# Tom_Casey.net
KiCad netlist of a schematic drawn in EAGLE
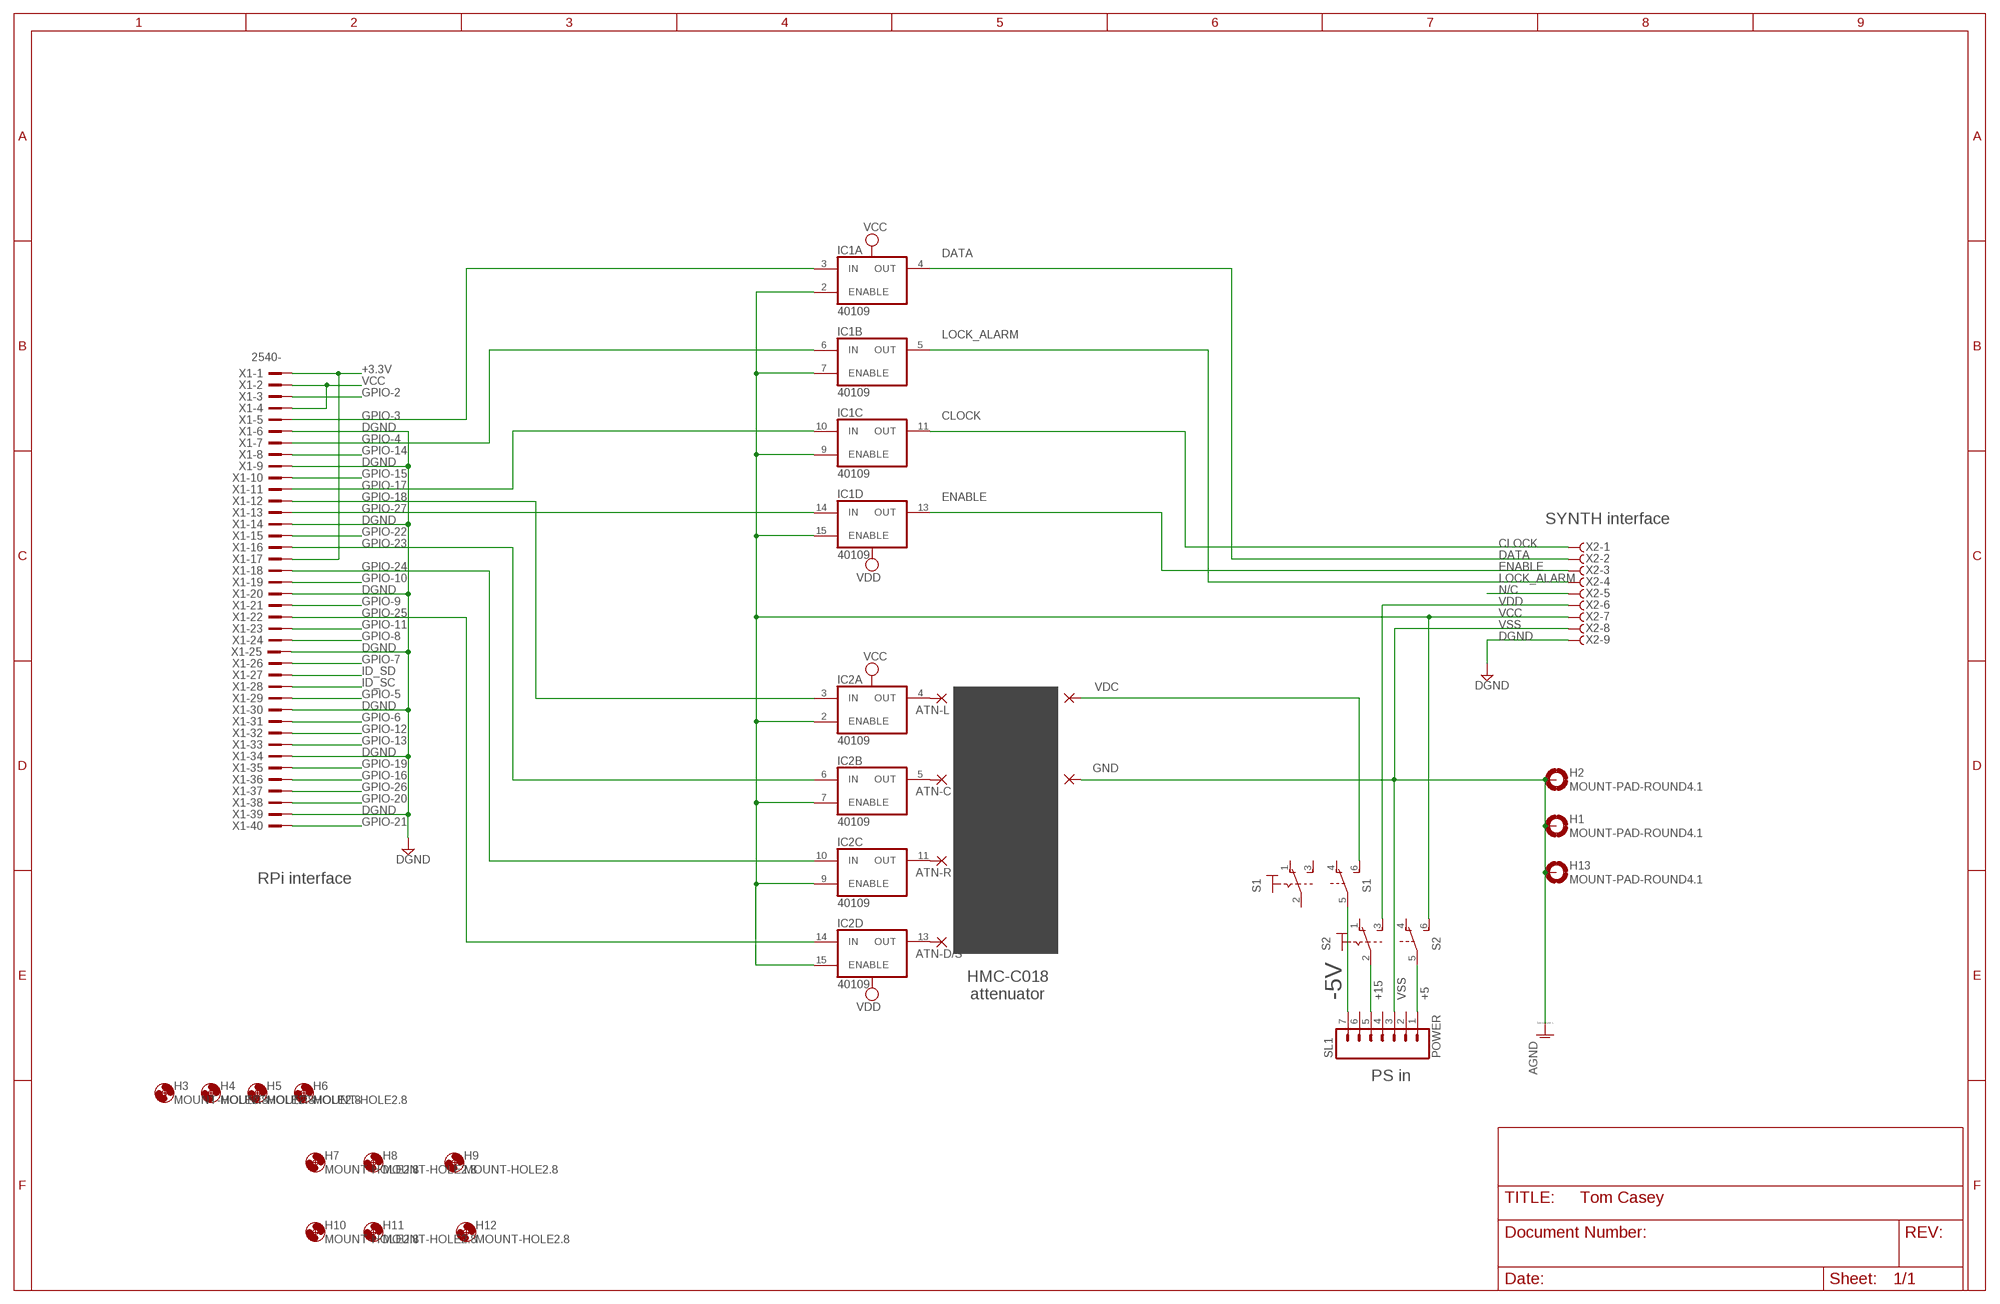
[diagram p0: schematic, sheet 1]

(export (version "E")
  (design (tool "Eeschema 10.0.6"))
  (components
    (comp (ref "ATN-C")
      (value "PAD-0400")
      (footprint "eagle-import:0400")
      (libsource (lib "eagle-import") (part "PAD-0400"))
    )
    (comp (ref "ATN-D/S")
      (value "PAD-0400")
      (footprint "eagle-import:0400")
      (libsource (lib "eagle-import") (part "PAD-0400"))
    )
    (comp (ref "ATN-L")
      (value "PAD-0400")
      (footprint "eagle-import:0400")
      (libsource (lib "eagle-import") (part "PAD-0400"))
    )
    (comp (ref "ATN-R")
      (value "PAD-0400")
      (footprint "eagle-import:0400")
      (libsource (lib "eagle-import") (part "PAD-0400"))
    )
    (comp (ref "GND")
      (value "PAD-0400")
      (footprint "eagle-import:0400")
      (libsource (lib "eagle-import") (part "PAD-0400"))
    )
    (comp (ref "H1")
      (value "MOUNT-PAD-ROUND4.1")
      (footprint "eagle-import:4,1-PAD")
      (libsource (lib "eagle-import") (part "MOUNT-PAD-ROUND4.1"))
    )
    (comp (ref "H2")
      (value "MOUNT-PAD-ROUND4.1")
      (footprint "eagle-import:4,1-PAD")
      (libsource (lib "eagle-import") (part "MOUNT-PAD-ROUND4.1"))
    )
    (comp (ref "H3")
      (value "MOUNT-HOLE2.8")
      (footprint "eagle-import:2,8")
      (libsource (lib "eagle-import") (part "MOUNT-HOLE2.8"))
    )
    (comp (ref "H4")
      (value "MOUNT-HOLE2.8")
      (footprint "eagle-import:2,8")
      (libsource (lib "eagle-import") (part "MOUNT-HOLE2.8"))
    )
    (comp (ref "H5")
      (value "MOUNT-HOLE2.8")
      (footprint "eagle-import:2,8")
      (libsource (lib "eagle-import") (part "MOUNT-HOLE2.8"))
    )
    (comp (ref "H6")
      (value "MOUNT-HOLE2.8")
      (footprint "eagle-import:2,8")
      (libsource (lib "eagle-import") (part "MOUNT-HOLE2.8"))
    )
    (comp (ref "H7")
      (value "MOUNT-HOLE2.8")
      (footprint "eagle-import:2,8")
      (libsource (lib "eagle-import") (part "MOUNT-HOLE2.8"))
    )
    (comp (ref "H8")
      (value "MOUNT-HOLE2.8")
      (footprint "eagle-import:2,8")
      (libsource (lib "eagle-import") (part "MOUNT-HOLE2.8"))
    )
    (comp (ref "H9")
      (value "MOUNT-HOLE2.8")
      (footprint "eagle-import:2,8")
      (libsource (lib "eagle-import") (part "MOUNT-HOLE2.8"))
    )
    (comp (ref "H10")
      (value "MOUNT-HOLE2.8")
      (footprint "eagle-import:2,8")
      (libsource (lib "eagle-import") (part "MOUNT-HOLE2.8"))
    )
    (comp (ref "H11")
      (value "MOUNT-HOLE2.8")
      (footprint "eagle-import:2,8")
      (libsource (lib "eagle-import") (part "MOUNT-HOLE2.8"))
    )
    (comp (ref "H12")
      (value "MOUNT-HOLE2.8")
      (footprint "eagle-import:2,8")
      (libsource (lib "eagle-import") (part "MOUNT-HOLE2.8"))
    )
    (comp (ref "H13")
      (value "MOUNT-PAD-ROUND4.1")
      (footprint "eagle-import:4,1-PAD")
      (libsource (lib "eagle-import") (part "MOUNT-PAD-ROUND4.1"))
    )
    (comp (ref "IC1")
      (value "40109")
      (footprint "eagle-import:DIL16")
      (libsource (lib "eagle-import") (part "40109"))
    )
    (comp (ref "IC2")
      (value "40109")
      (footprint "eagle-import:DIL16")
      (libsource (lib "eagle-import") (part "40109"))
    )
    (comp (ref "S1")
      (value "M9040P2")
      (footprint "eagle-import:M9040P2")
      (libsource (lib "eagle-import") (part "M9040P2"))
    )
    (comp (ref "S2")
      (value "M9040P2")
      (footprint "eagle-import:M9040P2")
      (libsource (lib "eagle-import") (part "M9040P2"))
    )
    (comp (ref "SL1")
      (value "POWER")
      (footprint "eagle-import:07P")
      (libsource (lib "eagle-import") (part "M07"))
    )
    (comp (ref "VDC")
      (value "PAD-0400")
      (footprint "eagle-import:0400")
      (libsource (lib "eagle-import") (part "PAD-0400"))
    )
    (comp (ref "X1")
      (value "2540-")
      (footprint "eagle-import:PAK100_2500-40")
      (libsource (lib "eagle-import") (part "2540-"))
    )
    (comp (ref "X2")
      (value "F09HPS")
      (footprint "eagle-import:F09HP")
      (libsource (lib "eagle-import") (part "F09?SHP"))
    )
  )
  (nets
    (net (code "1") (name "/+3.3V") (class "Default")
      (node (ref "X1") (pin "1") (pinfunction "KL_1") (pintype "passive"))
      (node (ref "X1") (pin "17") (pinfunction "KL_17") (pintype "passive"))
    )
    (net (code "2") (name "/+5") (class "Default")
      (node (ref "S2") (pin "5") (pinfunction "P_5") (pintype "passive"))
      (node (ref "SL1") (pin "1") (pinfunction "1_1") (pintype "passive"))
    )
    (net (code "3") (name "/+15") (class "Default")
      (node (ref "S2") (pin "2") (pinfunction "P_2") (pintype "passive"))
      (node (ref "SL1") (pin "5") (pinfunction "5_5") (pintype "passive"))
    )
    (net (code "4") (name "/-5V") (class "Default")
      (node (ref "S1") (pin "5") (pinfunction "P_5") (pintype "passive"))
      (node (ref "SL1") (pin "7") (pinfunction "7_7") (pintype "passive"))
    )
    (net (code "5") (name "/CLOCK") (class "Default")
      (node (ref "IC1") (pin "11") (pinfunction "OUT_11") (pintype "tri_state"))
      (node (ref "X2") (pin "1") (pinfunction "F_1") (pintype "passive"))
    )
    (net (code "6") (name "/DATA") (class "Default")
      (node (ref "IC1") (pin "4") (pinfunction "OUT_4") (pintype "tri_state"))
      (node (ref "X2") (pin "2") (pinfunction "F_2") (pintype "passive"))
    )
    (net (code "7") (name "/ENABLE") (class "Default")
      (node (ref "IC1") (pin "13") (pinfunction "OUT_13") (pintype "tri_state"))
      (node (ref "X2") (pin "3") (pinfunction "F_3") (pintype "passive"))
    )
    (net (code "8") (name "/GPIO-2") (class "Default")
      (node (ref "X1") (pin "3") (pinfunction "KL_3") (pintype "passive"))
    )
    (net (code "9") (name "/GPIO-3") (class "Default")
      (node (ref "IC1") (pin "3") (pinfunction "IN_3") (pintype "input"))
      (node (ref "X1") (pin "5") (pinfunction "KL_5") (pintype "passive"))
    )
    (net (code "10") (name "/GPIO-4") (class "Default")
      (node (ref "IC1") (pin "6") (pinfunction "IN_6") (pintype "input"))
      (node (ref "X1") (pin "7") (pinfunction "KL_7") (pintype "passive"))
    )
    (net (code "11") (name "/GPIO-5") (class "Default")
      (node (ref "X1") (pin "29") (pinfunction "KL_29") (pintype "passive"))
    )
    (net (code "12") (name "/GPIO-6") (class "Default")
      (node (ref "X1") (pin "31") (pinfunction "KL_31") (pintype "passive"))
    )
    (net (code "13") (name "/GPIO-7") (class "Default")
      (node (ref "X1") (pin "26") (pinfunction "KL_26") (pintype "passive"))
    )
    (net (code "14") (name "/GPIO-8") (class "Default")
      (node (ref "X1") (pin "24") (pinfunction "KL_24") (pintype "passive"))
    )
    (net (code "15") (name "/GPIO-9") (class "Default")
      (node (ref "X1") (pin "21") (pinfunction "KL_21") (pintype "passive"))
    )
    (net (code "16") (name "/GPIO-10") (class "Default")
      (node (ref "X1") (pin "19") (pinfunction "KL_19") (pintype "passive"))
    )
    (net (code "17") (name "/GPIO-11") (class "Default")
      (node (ref "X1") (pin "23") (pinfunction "KL_23") (pintype "passive"))
    )
    (net (code "18") (name "/GPIO-12") (class "Default")
      (node (ref "X1") (pin "32") (pinfunction "KL_32") (pintype "passive"))
    )
    (net (code "19") (name "/GPIO-13") (class "Default")
      (node (ref "X1") (pin "33") (pinfunction "KL_33") (pintype "passive"))
    )
    (net (code "20") (name "/GPIO-14") (class "Default")
      (node (ref "X1") (pin "8") (pinfunction "KL_8") (pintype "passive"))
    )
    (net (code "21") (name "/GPIO-15") (class "Default")
      (node (ref "X1") (pin "10") (pinfunction "KL_10") (pintype "passive"))
    )
    (net (code "22") (name "/GPIO-16") (class "Default")
      (node (ref "X1") (pin "36") (pinfunction "KL_36") (pintype "passive"))
    )
    (net (code "23") (name "/GPIO-17") (class "Default")
      (node (ref "IC1") (pin "10") (pinfunction "IN_10") (pintype "input"))
      (node (ref "X1") (pin "11") (pinfunction "KL_11") (pintype "passive"))
    )
    (net (code "24") (name "/GPIO-18") (class "Default")
      (node (ref "IC2") (pin "3") (pinfunction "IN_3") (pintype "input"))
      (node (ref "X1") (pin "12") (pinfunction "KL_12") (pintype "passive"))
    )
    (net (code "25") (name "/GPIO-19") (class "Default")
      (node (ref "X1") (pin "35") (pinfunction "KL_35") (pintype "passive"))
    )
    (net (code "26") (name "/GPIO-20") (class "Default")
      (node (ref "X1") (pin "38") (pinfunction "KL_38") (pintype "passive"))
    )
    (net (code "27") (name "/GPIO-21") (class "Default")
      (node (ref "X1") (pin "40") (pinfunction "KL_40") (pintype "passive"))
    )
    (net (code "28") (name "/GPIO-22") (class "Default")
      (node (ref "X1") (pin "15") (pinfunction "KL_15") (pintype "passive"))
    )
    (net (code "29") (name "/GPIO-23") (class "Default")
      (node (ref "IC2") (pin "6") (pinfunction "IN_6") (pintype "input"))
      (node (ref "X1") (pin "16") (pinfunction "KL_16") (pintype "passive"))
    )
    (net (code "30") (name "/GPIO-24") (class "Default")
      (node (ref "IC2") (pin "10") (pinfunction "IN_10") (pintype "input"))
      (node (ref "X1") (pin "18") (pinfunction "KL_18") (pintype "passive"))
    )
    (net (code "31") (name "/GPIO-25") (class "Default")
      (node (ref "IC2") (pin "14") (pinfunction "IN_14") (pintype "input"))
      (node (ref "X1") (pin "22") (pinfunction "KL_22") (pintype "passive"))
    )
    (net (code "32") (name "/GPIO-26") (class "Default")
      (node (ref "X1") (pin "37") (pinfunction "KL_37") (pintype "passive"))
    )
    (net (code "33") (name "/GPIO-27") (class "Default")
      (node (ref "IC1") (pin "14") (pinfunction "IN_14") (pintype "input"))
      (node (ref "X1") (pin "13") (pinfunction "KL_13") (pintype "passive"))
    )
    (net (code "34") (name "/ID_SC") (class "Default")
      (node (ref "X1") (pin "28") (pinfunction "KL_28") (pintype "passive"))
    )
    (net (code "35") (name "/ID_SD") (class "Default")
      (node (ref "X1") (pin "27") (pinfunction "KL_27") (pintype "passive"))
    )
    (net (code "36") (name "/LOCK_ALARM") (class "Default")
      (node (ref "IC1") (pin "5") (pinfunction "OUT_5") (pintype "tri_state"))
      (node (ref "X2") (pin "4") (pinfunction "F_4") (pintype "passive"))
    )
    (net (code "37") (name "/N{slash}C") (class "Default")
      (node (ref "X2") (pin "5") (pinfunction "F_5") (pintype "passive"))
    )
    (net (code "38") (name "AGND") (class "Default")
      (node (ref "GND") (pin "P$1") (pinfunction "P_P$1") (pintype "passive"))
      (node (ref "H1") (pin "B4,1") (pinfunction "MOUNT_B4,1") (pintype "passive"))
      (node (ref "H13") (pin "B4,1") (pinfunction "MOUNT_B4,1") (pintype "passive"))
      (node (ref "H2") (pin "B4,1") (pinfunction "MOUNT_B4,1") (pintype "passive"))
      (node (ref "SL1") (pin "3") (pinfunction "3_3") (pintype "passive"))
      (node (ref "X2") (pin "8") (pinfunction "F_8") (pintype "passive"))
    )
    (net (code "39") (name "DGND") (class "Default")
      (node (ref "X1") (pin "14") (pinfunction "KL_14") (pintype "passive"))
      (node (ref "X1") (pin "20") (pinfunction "KL_20") (pintype "passive"))
      (node (ref "X1") (pin "25") (pinfunction "KL_25") (pintype "passive"))
      (node (ref "X1") (pin "30") (pinfunction "KL_30") (pintype "passive"))
      (node (ref "X1") (pin "34") (pinfunction "KL_34") (pintype "passive"))
      (node (ref "X1") (pin "39") (pinfunction "KL_39") (pintype "passive"))
      (node (ref "X1") (pin "6") (pinfunction "KL_6") (pintype "passive"))
      (node (ref "X1") (pin "9") (pinfunction "KL_9") (pintype "passive"))
      (node (ref "X2") (pin "9") (pinfunction "F_9") (pintype "passive"))
    )
    (net (code "40") (name "Net-(ATN-C-P)") (class "Default")
      (node (ref "ATN-C") (pin "P$1") (pinfunction "P_P$1") (pintype "passive"))
      (node (ref "IC2") (pin "5") (pinfunction "OUT_5") (pintype "tri_state"))
    )
    (net (code "41") (name "Net-(ATN-D/S-P)") (class "Default")
      (node (ref "ATN-D/S") (pin "P$1") (pinfunction "P_P$1") (pintype "passive"))
      (node (ref "IC2") (pin "13") (pinfunction "OUT_13") (pintype "tri_state"))
    )
    (net (code "42") (name "Net-(ATN-L-P)") (class "Default")
      (node (ref "ATN-L") (pin "P$1") (pinfunction "P_P$1") (pintype "passive"))
      (node (ref "IC2") (pin "4") (pinfunction "OUT_4") (pintype "tri_state"))
    )
    (net (code "43") (name "Net-(ATN-R-P)") (class "Default")
      (node (ref "ATN-R") (pin "P$1") (pinfunction "P_P$1") (pintype "passive"))
      (node (ref "IC2") (pin "11") (pinfunction "OUT_11") (pintype "tri_state"))
    )
    (net (code "44") (name "Net-(S1B-S)") (class "Default")
      (node (ref "S1") (pin "6") (pinfunction "S_6") (pintype "passive"))
      (node (ref "VDC") (pin "P$1") (pinfunction "P_P$1") (pintype "passive"))
    )
    (net (code "45") (name "VCC") (class "Default")
      (node (ref "IC1") (pin "15") (pinfunction "ENABLE_15") (pintype "input"))
      (node (ref "IC1") (pin "2") (pinfunction "ENABLE_2") (pintype "input"))
      (node (ref "IC1") (pin "7") (pinfunction "ENABLE_7") (pintype "input"))
      (node (ref "IC1") (pin "9") (pinfunction "ENABLE_9") (pintype "input"))
      (node (ref "IC2") (pin "15") (pinfunction "ENABLE_15") (pintype "input"))
      (node (ref "IC2") (pin "2") (pinfunction "ENABLE_2") (pintype "input"))
      (node (ref "IC2") (pin "7") (pinfunction "ENABLE_7") (pintype "input"))
      (node (ref "IC2") (pin "9") (pinfunction "ENABLE_9") (pintype "input"))
      (node (ref "S2") (pin "6") (pinfunction "S_6") (pintype "passive"))
      (node (ref "X1") (pin "2") (pinfunction "KL_2") (pintype "passive"))
      (node (ref "X1") (pin "4") (pinfunction "KL_4") (pintype "passive"))
      (node (ref "X2") (pin "7") (pinfunction "F_7") (pintype "passive"))
    )
    (net (code "46") (name "VDD") (class "Default")
      (node (ref "S2") (pin "3") (pinfunction "S_3") (pintype "passive"))
      (node (ref "X2") (pin "6") (pinfunction "F_6") (pintype "passive"))
    )
    (net (code "47") (name "unconnected-(S1A-O-Pad1)") (class "Default")
      (node (ref "S1") (pin "1") (pinfunction "O_1") (pintype "passive"))
    )
    (net (code "48") (name "unconnected-(S1A-P-Pad2)") (class "Default")
      (node (ref "S1") (pin "2") (pinfunction "P_2") (pintype "passive"))
    )
    (net (code "49") (name "unconnected-(S1A-S-Pad3)") (class "Default")
      (node (ref "S1") (pin "3") (pinfunction "S_3") (pintype "passive"))
    )
    (net (code "50") (name "unconnected-(S1B-O-Pad4)") (class "Default")
      (node (ref "S1") (pin "4") (pinfunction "O_4") (pintype "passive"))
    )
    (net (code "51") (name "unconnected-(S2A-O-Pad1)") (class "Default")
      (node (ref "S2") (pin "1") (pinfunction "O_1") (pintype "passive"))
    )
    (net (code "52") (name "unconnected-(S2B-O-Pad4)") (class "Default")
      (node (ref "S2") (pin "4") (pinfunction "O_4") (pintype "passive"))
    )
    (net (code "53") (name "unconnected-(SL1-Pad2)") (class "Default")
      (node (ref "SL1") (pin "2") (pinfunction "2_2") (pintype "passive"))
    )
    (net (code "54") (name "unconnected-(SL1-Pad4)") (class "Default")
      (node (ref "SL1") (pin "4") (pinfunction "4_4") (pintype "passive"))
    )
    (net (code "55") (name "unconnected-(SL1-Pad6)") (class "Default")
      (node (ref "SL1") (pin "6") (pinfunction "6_6") (pintype "passive"))
    )
  )
)
